# coaxial-port.net
KiCad netlist of a schematic drawn in Altium Designer
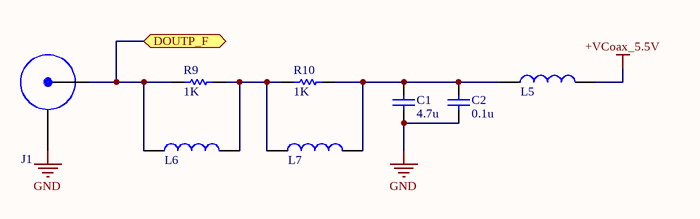
[diagram p0: coaxial-port.SchDoc]

(export (version "E")
  (design (tool "Eeschema 10.0.6"))
  (components
    (comp (ref "C1")
      (value "4.7u")
      (footprint "Cap-0603")
      (description "Capacitor")
      (fields (field (name "Comment") "X7R Ceramic") (field (name "PUBLISHER") "Altium Limited"))
      (libsource (lib "Miscellaneous Devices") (part "Cap"))
    )
    (comp (ref "C2")
      (value "0.1u")
      (footprint "Cap-0603")
      (description "Capacitor")
      (fields (field (name "Comment") "X7R Ceramic") (field (name "PUBLISHER") "Altium Limited"))
      (libsource (lib "Miscellaneous Devices") (part "Cap"))
    )
    (comp (ref "J1")
      (value "Coax Connector")
      (footprint "SMA_132134-10-ND")
      (libsource (lib "DA_Component_Library") (part "Coax Connector"))
    )
    (comp (ref "L5")
      (value "Ferrite Bead")
      (footprint "BLM18KG601SN1D")
      (libsource (lib "DA_Component_Library") (part "Ferrite Bead"))
    )
    (comp (ref "L6")
      (value "Ferrite Bead")
      (footprint "CIG21L4R7MNE")
      (libsource (lib "DA_Component_Library") (part "Ferrite Bead"))
    )
    (comp (ref "L7")
      (value "Ferrite Bead")
      (footprint "CBC3225T101MR")
      (libsource (lib "DA_Component_Library") (part "Ferrite Bead"))
    )
    (comp (ref "R9")
      (value "1K")
      (footprint "Res_0402")
      (description "Resistor")
      (fields (field (name "Comment") "Res1") (field (name "PUBLISHER") "Altium Limited"))
      (libsource (lib "Miscellaneous Devices") (part "Res1"))
    )
    (comp (ref "R10")
      (value "1K")
      (footprint "Res_0402")
      (description "Resistor")
      (fields (field (name "Comment") "Res1") (field (name "PUBLISHER") "Altium Limited"))
      (libsource (lib "Miscellaneous Devices") (part "Res1"))
    )
  )
  (nets
    (net (code "1") (name "+VCoax_5.5V") (class "Default")
      (node (ref "L5") (pin "2") (pinfunction "2_2") (pintype "passive"))
    )
    (net (code "2") (name "/DOUTP_F") (class "Default")
      (node (ref "J1") (pin "0") (pinfunction "0_0") (pintype "passive"))
      (node (ref "L6") (pin "1") (pinfunction "1_1") (pintype "passive"))
      (node (ref "R9") (pin "2") (pinfunction "2_2") (pintype "passive"))
    )
    (net (code "3") (name "GND") (class "Default")
      (node (ref "C1") (pin "1") (pinfunction "1_1") (pintype "passive"))
      (node (ref "C2") (pin "1") (pinfunction "1_1") (pintype "passive"))
      (node (ref "J1") (pin "1") (pinfunction "1_1") (pintype "passive"))
    )
    (net (code "4") (name "Net-(C1-Pad2)") (class "Default")
      (node (ref "C1") (pin "2") (pinfunction "2_2") (pintype "passive"))
      (node (ref "C2") (pin "2") (pinfunction "2_2") (pintype "passive"))
      (node (ref "L5") (pin "1") (pinfunction "1_1") (pintype "passive"))
      (node (ref "L7") (pin "2") (pinfunction "2_2") (pintype "passive"))
      (node (ref "R10") (pin "1") (pinfunction "1_1") (pintype "passive"))
    )
    (net (code "5") (name "Net-(L6-Pad2)") (class "Default")
      (node (ref "L6") (pin "2") (pinfunction "2_2") (pintype "passive"))
      (node (ref "L7") (pin "1") (pinfunction "1_1") (pintype "passive"))
      (node (ref "R10") (pin "2") (pinfunction "2_2") (pintype "passive"))
      (node (ref "R9") (pin "1") (pinfunction "1_1") (pintype "passive"))
    )
  )
)
